# programmer_pcb2.net
KiCad netlist of a schematic drawn in EAGLE
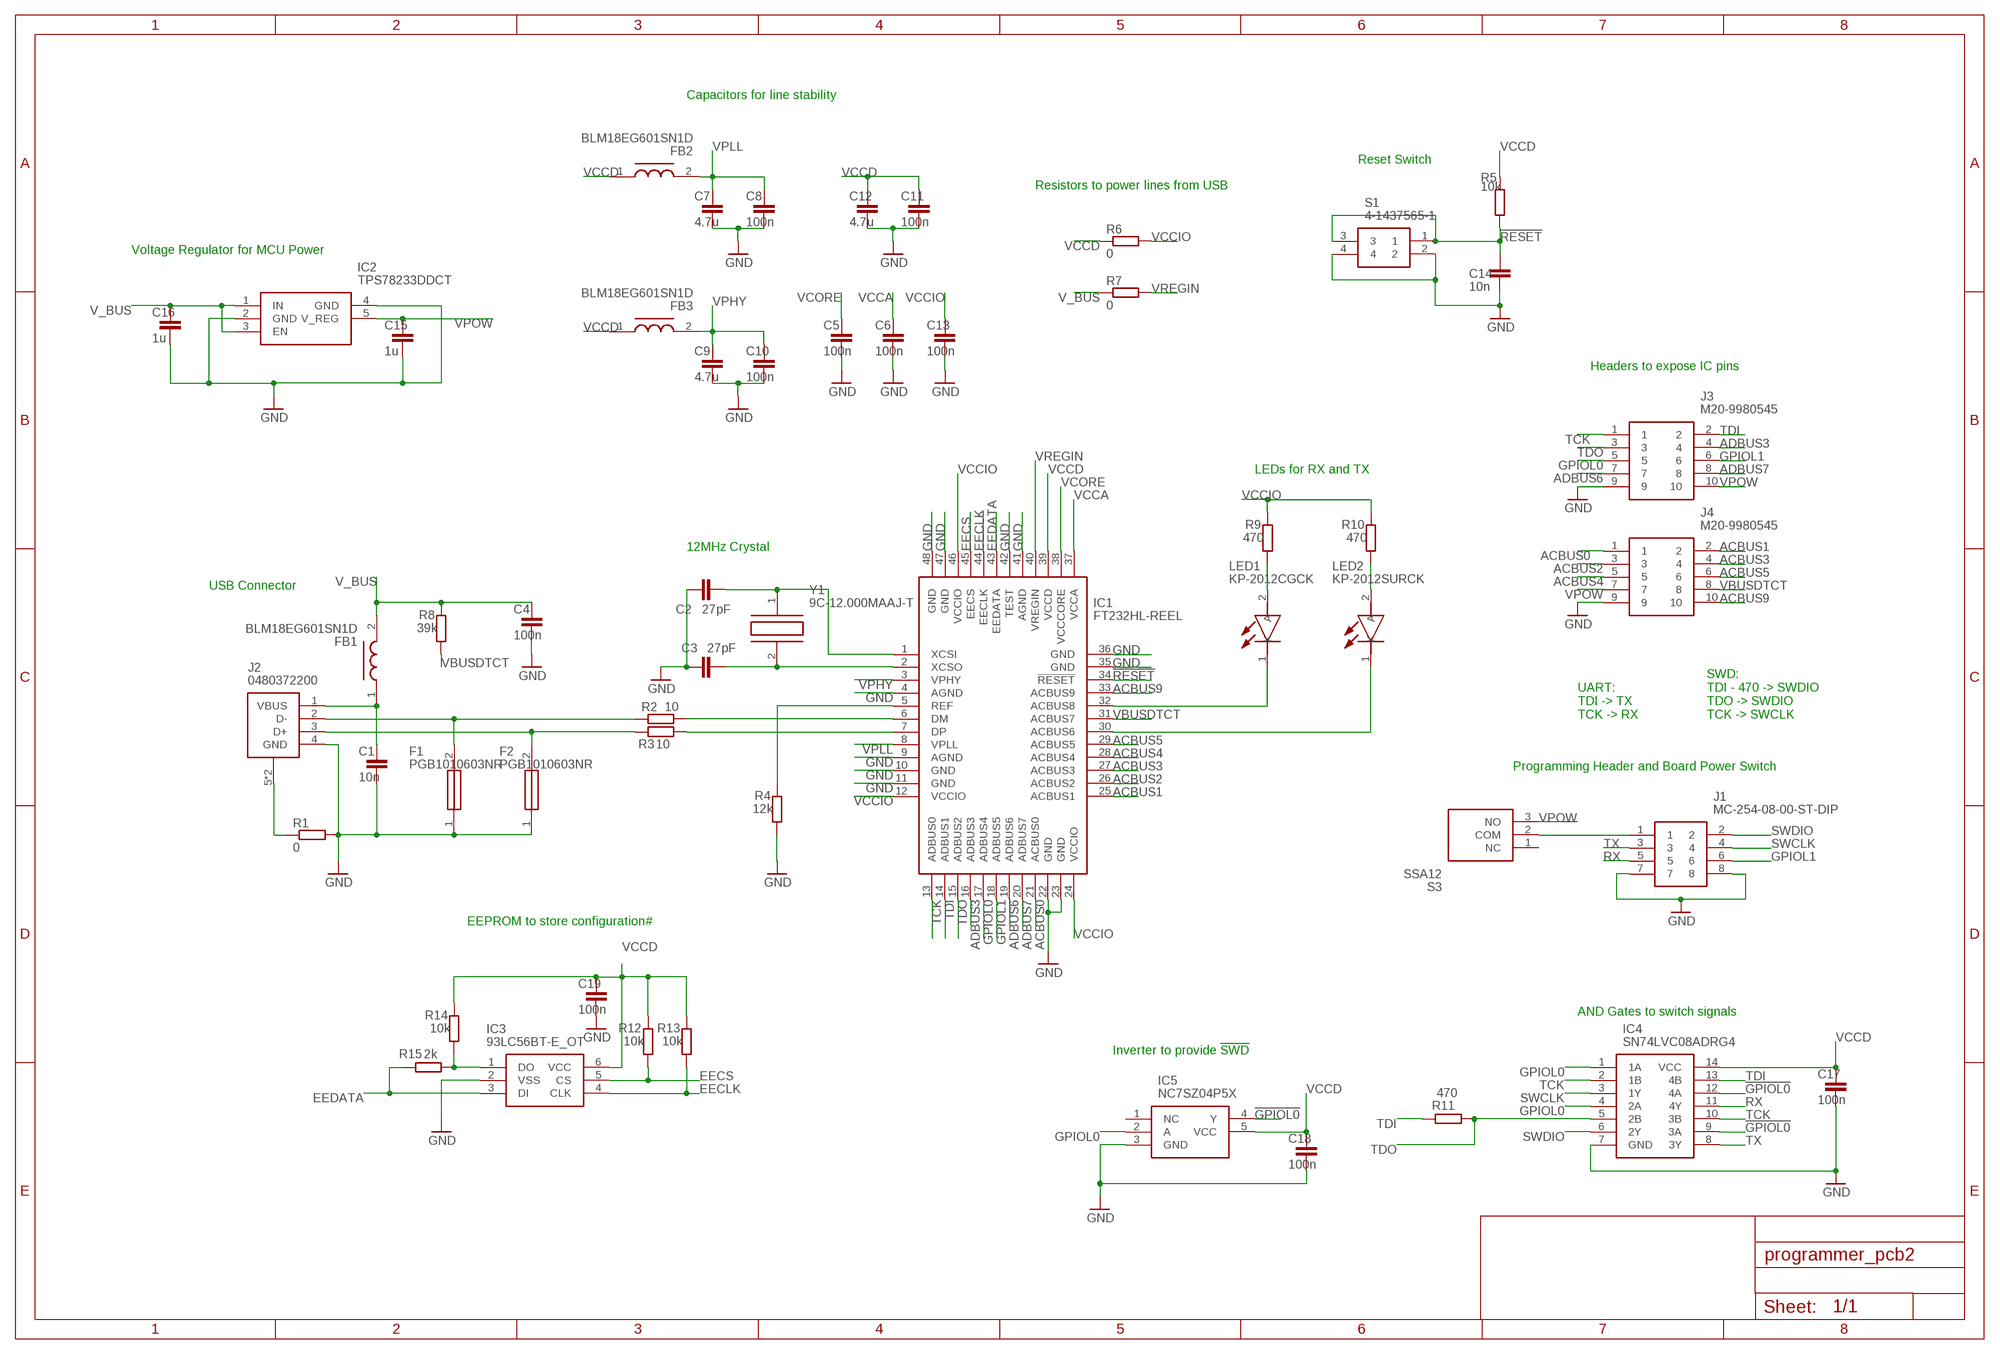
[diagram p0: schematic, sheet 1]

(export (version "E")
  (design (tool "Eeschema 10.0.6"))
  (components
    (comp (ref "C1")
      (value "10n")
      (footprint "eagle-import:C0805")
      (libsource (lib "eagle-import") (part "C-EUC0805"))
    )
    (comp (ref "C2")
      (value "27pF")
      (footprint "eagle-import:C0805")
      (libsource (lib "eagle-import") (part "C-EUC0805"))
    )
    (comp (ref "C3")
      (value "27pF")
      (footprint "eagle-import:C0805")
      (libsource (lib "eagle-import") (part "C-EUC0805"))
    )
    (comp (ref "C4")
      (value "100n")
      (footprint "eagle-import:C0805")
      (libsource (lib "eagle-import") (part "C-EUC0805"))
    )
    (comp (ref "C5")
      (value "100n")
      (footprint "eagle-import:C0805")
      (libsource (lib "eagle-import") (part "C-EUC0805"))
    )
    (comp (ref "C6")
      (value "100n")
      (footprint "eagle-import:C0805")
      (libsource (lib "eagle-import") (part "C-EUC0805"))
    )
    (comp (ref "C7")
      (value "4.7u")
      (footprint "eagle-import:C0805")
      (libsource (lib "eagle-import") (part "C-EUC0805"))
    )
    (comp (ref "C8")
      (value "100n")
      (footprint "eagle-import:C0805")
      (libsource (lib "eagle-import") (part "C-EUC0805"))
    )
    (comp (ref "C9")
      (value "4.7u")
      (footprint "eagle-import:C0805")
      (libsource (lib "eagle-import") (part "C-EUC0805"))
    )
    (comp (ref "C10")
      (value "100n")
      (footprint "eagle-import:C0805")
      (libsource (lib "eagle-import") (part "C-EUC0805"))
    )
    (comp (ref "C11")
      (value "100n")
      (footprint "eagle-import:C0805")
      (libsource (lib "eagle-import") (part "C-EUC0805"))
    )
    (comp (ref "C12")
      (value "4.7u")
      (footprint "eagle-import:C0805")
      (libsource (lib "eagle-import") (part "C-EUC0805"))
    )
    (comp (ref "C13")
      (value "100n")
      (footprint "eagle-import:C0805")
      (libsource (lib "eagle-import") (part "C-EUC0805"))
    )
    (comp (ref "C14")
      (value "10n")
      (footprint "eagle-import:C0805")
      (libsource (lib "eagle-import") (part "C-EUC0805"))
    )
    (comp (ref "C15")
      (value "1u")
      (footprint "eagle-import:C0805")
      (libsource (lib "eagle-import") (part "C-EUC0805"))
    )
    (comp (ref "C16")
      (value "1u")
      (footprint "eagle-import:C0805")
      (libsource (lib "eagle-import") (part "C-EUC0805"))
    )
    (comp (ref "C17")
      (value "100n")
      (footprint "eagle-import:C0805")
      (libsource (lib "eagle-import") (part "C-EUC0805"))
    )
    (comp (ref "C18")
      (value "100n")
      (footprint "eagle-import:C0805")
      (libsource (lib "eagle-import") (part "C-EUC0805"))
    )
    (comp (ref "C19")
      (value "100n")
      (footprint "eagle-import:C0805")
      (libsource (lib "eagle-import") (part "C-EUC0805"))
    )
    (comp (ref "F1")
      (value "PGB1010603NR")
      (footprint "eagle-import:FUSC1708X36N")
      (fields (field (name "MOUSER_PART_NUMBER") "576-PGB1010603NR"))
      (libsource (lib "eagle-import") (part "PGB1010603NR"))
    )
    (comp (ref "F2")
      (value "PGB1010603NR")
      (footprint "eagle-import:FUSC1708X36N")
      (fields (field (name "MOUSER_PART_NUMBER") "576-PGB1010603NR"))
      (libsource (lib "eagle-import") (part "PGB1010603NR"))
    )
    (comp (ref "FB1")
      (value "BLM18EG601SN1D")
      (footprint "eagle-import:BLM18EG121SH1D")
      (fields (field (name "MOUSER_PART_NUMBER") "81-BLM18EG601SN1D"))
      (libsource (lib "eagle-import") (part "BLM18EG601SN1D"))
    )
    (comp (ref "FB2")
      (value "BLM18EG601SN1D")
      (footprint "eagle-import:BLM18EG121SH1D")
      (fields (field (name "MOUSER_PART_NUMBER") "81-BLM18EG601SN1D"))
      (libsource (lib "eagle-import") (part "BLM18EG601SN1D"))
    )
    (comp (ref "FB3")
      (value "BLM18EG601SN1D")
      (footprint "eagle-import:BLM18EG121SH1D")
      (fields (field (name "MOUSER_PART_NUMBER") "81-BLM18EG601SN1D"))
      (libsource (lib "eagle-import") (part "BLM18EG601SN1D"))
    )
    (comp (ref "IC1")
      (value "FT232HL-REEL")
      (footprint "eagle-import:QFP50P900X900X160-48N")
      (fields (field (name "MOUSER_PART_NUMBER") "895-FT232HL-REEL"))
      (libsource (lib "eagle-import") (part "FT232HL-REEL"))
    )
    (comp (ref "IC2")
      (value "TPS78233DDCT")
      (footprint "eagle-import:SOT95P280X110-5N")
      (fields (field (name "MOUSER_PART_NUMBER") "595-TPS78233DDCT"))
      (libsource (lib "eagle-import") (part "TPS78233DDCT"))
    )
    (comp (ref "IC3")
      (value "93LC56BT-E_OT")
      (footprint "eagle-import:SOT95P270X145-6N")
      (fields
        (field (name "ARROW_PART_NUMBER") "93LC56BT-E/OT")
        (field (name "MOUSER_PART_NUMBER") "579-93LC56BT-E/OT")
      )
      (libsource (lib "eagle-import") (part "93LC56BT-E_OT"))
    )
    (comp (ref "IC4")
      (value "SN74LVC08ADRG4")
      (footprint "eagle-import:SOIC127P600X175-14N")
      (fields (field (name "MOUSER_PART_NUMBER") "595-SN74LVC08ADRG4"))
      (libsource (lib "eagle-import") (part "SN74LVC08ADRG4"))
    )
    (comp (ref "IC5")
      (value "NC7SZ04P5X")
      (footprint "eagle-import:SOT65P210X110-5N")
      (fields (field (name "MOUSER_PART_NUMBER") "512-NC7SZ04P5X"))
      (libsource (lib "eagle-import") (part "NC7SZ04P5X"))
    )
    (comp (ref "J1")
      (value "MC-254-08-00-ST-DIP")
      (footprint "eagle-import:MC2540800STDIP")
      (libsource (lib "eagle-import") (part "MC-254-08-00-ST-DIP"))
    )
    (comp (ref "J2")
      (value "0480372200")
      (footprint "eagle-import:0480372200")
      (libsource (lib "eagle-import") (part "0480372200"))
    )
    (comp (ref "J3")
      (value "M20-9980545")
      (footprint "eagle-import:HDRV10W80P254_2X5_1270X508X864")
      (fields (field (name "MOUSER_PART_NUMBER") "855-M20-9980545"))
      (libsource (lib "eagle-import") (part "M20-9980545"))
    )
    (comp (ref "J4")
      (value "M20-9980545")
      (footprint "eagle-import:HDRV10W80P254_2X5_1270X508X864")
      (fields (field (name "MOUSER_PART_NUMBER") "855-M20-9980545"))
      (libsource (lib "eagle-import") (part "M20-9980545"))
    )
    (comp (ref "LED1")
      (value "KP-2012CGCK")
      (footprint "eagle-import:LEDC2012X110N")
      (fields (field (name "RS_PART_NUMBER") "8610037P"))
      (libsource (lib "eagle-import") (part "KP-2012CGCK"))
    )
    (comp (ref "LED2")
      (value "KP-2012SURCK")
      (footprint "eagle-import:LEDC2012X110N")
      (fields
        (field (name "MANUFACTURER_PART_NUMBER") "KP-2012CGCK")
        (field (name "RS_PART_NUMBER") "8610037P")
      )
      (libsource (lib "eagle-import") (part "KP-2012SURCK"))
    )
    (comp (ref "R1")
      (value "0")
      (footprint "eagle-import:R0603")
      (libsource (lib "eagle-import") (part "R-EU_R0603"))
    )
    (comp (ref "R2")
      (value "10")
      (footprint "eagle-import:R0603")
      (libsource (lib "eagle-import") (part "R-EU_R0603"))
    )
    (comp (ref "R3")
      (value "10")
      (footprint "eagle-import:R0603")
      (libsource (lib "eagle-import") (part "R-EU_R0603"))
    )
    (comp (ref "R4")
      (value "12k")
      (footprint "eagle-import:R0603")
      (libsource (lib "eagle-import") (part "R-EU_R0603"))
    )
    (comp (ref "R5")
      (value "10k")
      (footprint "eagle-import:R0603")
      (libsource (lib "eagle-import") (part "R-EU_R0603"))
    )
    (comp (ref "R6")
      (value "0")
      (footprint "eagle-import:R0603")
      (libsource (lib "eagle-import") (part "R-EU_R0603"))
    )
    (comp (ref "R7")
      (value "0")
      (footprint "eagle-import:R0603")
      (libsource (lib "eagle-import") (part "R-EU_R0603"))
    )
    (comp (ref "R8")
      (value "39k")
      (footprint "eagle-import:R0603")
      (libsource (lib "eagle-import") (part "R-EU_R0603"))
    )
    (comp (ref "R9")
      (value "470")
      (footprint "eagle-import:R0603")
      (libsource (lib "eagle-import") (part "R-EU_R0603"))
    )
    (comp (ref "R10")
      (value "470")
      (footprint "eagle-import:R0603")
      (libsource (lib "eagle-import") (part "R-EU_R0603"))
    )
    (comp (ref "R11")
      (value "470")
      (footprint "eagle-import:R0603")
      (libsource (lib "eagle-import") (part "R-EU_R0603"))
    )
    (comp (ref "R12")
      (value "10k")
      (footprint "eagle-import:R0603")
      (libsource (lib "eagle-import") (part "R-EU_R0603"))
    )
    (comp (ref "R13")
      (value "10k")
      (footprint "eagle-import:R0603")
      (libsource (lib "eagle-import") (part "R-EU_R0603"))
    )
    (comp (ref "R14")
      (value "10k")
      (footprint "eagle-import:R0603")
      (libsource (lib "eagle-import") (part "R-EU_R0603"))
    )
    (comp (ref "R15")
      (value "2k")
      (footprint "eagle-import:R0603")
      (libsource (lib "eagle-import") (part "R-EU_R0603"))
    )
    (comp (ref "S1")
      (value "4-1437565-1")
      (footprint "eagle-import:FSM-SWITCH")
      (fields (field (name "RS_PART_NUMBER") "4791508P"))
      (libsource (lib "eagle-import") (part "4-1437565-1"))
    )
    (comp (ref "S3")
      (value "SSA12")
      (footprint "eagle-import:SSA12")
      (fields (field (name "RS_PART_NUMBER") "7182326P"))
      (libsource (lib "eagle-import") (part "SSA12"))
    )
    (comp (ref "Y1")
      (value "9C-12.000MAAJ-T")
      (footprint "eagle-import:SMD-HC-49-S")
      (fields
        (field (name "ARROW_PART_NUMBER") "9C-8.000MAAJ-T")
        (field (name "MOUSER_PART_NUMBER") "717-9C-8.000MAAJ-T")
      )
      (libsource (lib "eagle-import") (part "9C-12.000MAAJ-T"))
    )
  )
  (nets
    (net (code "1") (name "/ACBUS0") (class "Default")
      (node (ref "IC1") (pin "21") (pinfunction "ACBUS0_21") (pintype "bidirectional"))
      (node (ref "J4") (pin "1") (pinfunction "1_1") (pintype "bidirectional"))
    )
    (net (code "2") (name "/ACBUS1") (class "Default")
      (node (ref "IC1") (pin "25") (pinfunction "ACBUS1_25") (pintype "bidirectional"))
      (node (ref "J4") (pin "2") (pinfunction "2_2") (pintype "bidirectional"))
    )
    (net (code "3") (name "/ACBUS2") (class "Default")
      (node (ref "IC1") (pin "26") (pinfunction "ACBUS2_26") (pintype "bidirectional"))
      (node (ref "J4") (pin "3") (pinfunction "3_3") (pintype "bidirectional"))
    )
    (net (code "4") (name "/ACBUS3") (class "Default")
      (node (ref "IC1") (pin "27") (pinfunction "ACBUS3_27") (pintype "bidirectional"))
      (node (ref "J4") (pin "4") (pinfunction "4_4") (pintype "bidirectional"))
    )
    (net (code "5") (name "/ACBUS4") (class "Default")
      (node (ref "IC1") (pin "28") (pinfunction "ACBUS4_28") (pintype "bidirectional"))
      (node (ref "J4") (pin "5") (pinfunction "5_5") (pintype "bidirectional"))
    )
    (net (code "6") (name "/ACBUS5") (class "Default")
      (node (ref "IC1") (pin "29") (pinfunction "ACBUS5_29") (pintype "bidirectional"))
      (node (ref "J4") (pin "6") (pinfunction "6_6") (pintype "bidirectional"))
    )
    (net (code "7") (name "/ACBUS9") (class "Default")
      (node (ref "IC1") (pin "33") (pinfunction "ACBUS9_33") (pintype "bidirectional"))
      (node (ref "J4") (pin "10") (pinfunction "10_10") (pintype "bidirectional"))
    )
    (net (code "8") (name "/ADBUS3") (class "Default")
      (node (ref "IC1") (pin "16") (pinfunction "ADBUS3_16") (pintype "bidirectional"))
      (node (ref "J3") (pin "4") (pinfunction "4_4") (pintype "bidirectional"))
    )
    (net (code "9") (name "/ADBUS6") (class "Default")
      (node (ref "IC1") (pin "19") (pinfunction "ADBUS6_19") (pintype "bidirectional"))
      (node (ref "J3") (pin "7") (pinfunction "7_7") (pintype "bidirectional"))
    )
    (net (code "10") (name "/ADBUS7") (class "Default")
      (node (ref "IC1") (pin "20") (pinfunction "ADBUS7_20") (pintype "bidirectional"))
      (node (ref "J3") (pin "8") (pinfunction "8_8") (pintype "bidirectional"))
    )
    (net (code "11") (name "/EECLK") (class "Default")
      (node (ref "IC1") (pin "44") (pinfunction "EECLK_44") (pintype "input"))
      (node (ref "IC3") (pin "4") (pinfunction "CLK_4") (pintype "bidirectional"))
      (node (ref "R13") (pin "1") (pinfunction "1_1") (pintype "passive"))
    )
    (net (code "12") (name "/EECS") (class "Default")
      (node (ref "IC1") (pin "45") (pinfunction "EECS_45") (pintype "input"))
      (node (ref "IC3") (pin "5") (pinfunction "CS_5") (pintype "bidirectional"))
      (node (ref "R12") (pin "1") (pinfunction "1_1") (pintype "passive"))
    )
    (net (code "13") (name "/EEDATA") (class "Default")
      (node (ref "IC1") (pin "43") (pinfunction "EEDATA_43") (pintype "bidirectional"))
      (node (ref "IC3") (pin "3") (pinfunction "DI_3") (pintype "bidirectional"))
      (node (ref "R15") (pin "1") (pinfunction "1_1") (pintype "passive"))
    )
    (net (code "14") (name "/GPIOL0") (class "Default")
      (node (ref "IC1") (pin "17") (pinfunction "ADBUS4_17") (pintype "bidirectional"))
      (node (ref "IC4") (pin "1") (pinfunction "1A_1") (pintype "bidirectional"))
      (node (ref "IC4") (pin "4") (pinfunction "2A_4") (pintype "bidirectional"))
      (node (ref "IC5") (pin "2") (pinfunction "A_2") (pintype "bidirectional"))
      (node (ref "J3") (pin "5") (pinfunction "5_5") (pintype "bidirectional"))
    )
    (net (code "15") (name "/GPIOL1") (class "Default")
      (node (ref "IC1") (pin "18") (pinfunction "ADBUS5_18") (pintype "bidirectional"))
      (node (ref "J1") (pin "6") (pinfunction "6_6") (pintype "bidirectional"))
      (node (ref "J3") (pin "6") (pinfunction "6_6") (pintype "bidirectional"))
    )
    (net (code "16") (name "/RX") (class "Default")
      (node (ref "IC4") (pin "11") (pinfunction "4Y_11") (pintype "bidirectional"))
      (node (ref "J1") (pin "5") (pinfunction "5_5") (pintype "bidirectional"))
    )
    (net (code "17") (name "/SWCLK") (class "Default")
      (node (ref "IC4") (pin "3") (pinfunction "1Y_3") (pintype "bidirectional"))
      (node (ref "J1") (pin "4") (pinfunction "4_4") (pintype "bidirectional"))
    )
    (net (code "18") (name "/SWDIO") (class "Default")
      (node (ref "IC4") (pin "6") (pinfunction "2Y_6") (pintype "bidirectional"))
      (node (ref "J1") (pin "2") (pinfunction "2_2") (pintype "bidirectional"))
    )
    (net (code "19") (name "/TCK") (class "Default")
      (node (ref "IC1") (pin "13") (pinfunction "ADBUS0_13") (pintype "bidirectional"))
      (node (ref "IC4") (pin "10") (pinfunction "3B_10") (pintype "bidirectional"))
      (node (ref "IC4") (pin "2") (pinfunction "1B_2") (pintype "bidirectional"))
      (node (ref "J3") (pin "1") (pinfunction "1_1") (pintype "bidirectional"))
    )
    (net (code "20") (name "/TDI") (class "Default")
      (node (ref "IC1") (pin "14") (pinfunction "ADBUS1_14") (pintype "bidirectional"))
      (node (ref "IC4") (pin "13") (pinfunction "4B_13") (pintype "bidirectional"))
      (node (ref "J3") (pin "2") (pinfunction "2_2") (pintype "bidirectional"))
      (node (ref "R11") (pin "1") (pinfunction "1_1") (pintype "passive"))
    )
    (net (code "21") (name "/TDO") (class "Default")
      (node (ref "IC1") (pin "15") (pinfunction "ADBUS2_15") (pintype "bidirectional"))
      (node (ref "IC4") (pin "5") (pinfunction "2B_5") (pintype "bidirectional"))
      (node (ref "J3") (pin "3") (pinfunction "3_3") (pintype "bidirectional"))
      (node (ref "R11") (pin "2") (pinfunction "2_2") (pintype "passive"))
    )
    (net (code "22") (name "/TX") (class "Default")
      (node (ref "IC4") (pin "8") (pinfunction "3Y_8") (pintype "bidirectional"))
      (node (ref "J1") (pin "3") (pinfunction "3_3") (pintype "bidirectional"))
    )
    (net (code "23") (name "/VBUSDTCT") (class "Default")
      (node (ref "IC1") (pin "31") (pinfunction "ACBUS7_31") (pintype "bidirectional"))
      (node (ref "J4") (pin "8") (pinfunction "8_8") (pintype "bidirectional"))
      (node (ref "R8") (pin "1") (pinfunction "1_1") (pintype "passive"))
    )
    (net (code "24") (name "/VCCA") (class "Default")
      (node (ref "C6") (pin "1") (pinfunction "1_1") (pintype "passive"))
      (node (ref "IC1") (pin "37") (pinfunction "VCCA_37") (pintype "power_in"))
    )
    (net (code "25") (name "/VCCD") (class "Default")
      (node (ref "C11") (pin "1") (pinfunction "1_1") (pintype "passive"))
      (node (ref "C12") (pin "1") (pinfunction "1_1") (pintype "passive"))
      (node (ref "C17") (pin "1") (pinfunction "1_1") (pintype "passive"))
      (node (ref "C18") (pin "1") (pinfunction "1_1") (pintype "passive"))
      (node (ref "C19") (pin "1") (pinfunction "1_1") (pintype "passive"))
      (node (ref "FB2") (pin "1") (pinfunction "1_1") (pintype "bidirectional"))
      (node (ref "FB3") (pin "1") (pinfunction "1_1") (pintype "bidirectional"))
      (node (ref "IC1") (pin "39") (pinfunction "VCCD_39") (pintype "power_in"))
      (node (ref "IC3") (pin "6") (pinfunction "VCC_6") (pintype "bidirectional"))
      (node (ref "IC4") (pin "14") (pinfunction "VCC_14") (pintype "bidirectional"))
      (node (ref "IC5") (pin "5") (pinfunction "VCC_5") (pintype "bidirectional"))
      (node (ref "R12") (pin "2") (pinfunction "2_2") (pintype "passive"))
      (node (ref "R13") (pin "2") (pinfunction "2_2") (pintype "passive"))
      (node (ref "R14") (pin "2") (pinfunction "2_2") (pintype "passive"))
      (node (ref "R5") (pin "2") (pinfunction "2_2") (pintype "passive"))
      (node (ref "R6") (pin "1") (pinfunction "1_1") (pintype "passive"))
    )
    (net (code "26") (name "/VCCIO") (class "Default")
      (node (ref "C13") (pin "1") (pinfunction "1_1") (pintype "passive"))
      (node (ref "IC1") (pin "12") (pinfunction "VCCIO_12") (pintype "power_in"))
      (node (ref "IC1") (pin "24") (pinfunction "VCCIO_24") (pintype "power_in"))
      (node (ref "IC1") (pin "46") (pinfunction "VCCIO_46") (pintype "power_in"))
      (node (ref "R10") (pin "2") (pinfunction "2_2") (pintype "passive"))
      (node (ref "R6") (pin "2") (pinfunction "2_2") (pintype "passive"))
      (node (ref "R9") (pin "2") (pinfunction "2_2") (pintype "passive"))
    )
    (net (code "27") (name "/VCORE") (class "Default")
      (node (ref "C5") (pin "1") (pinfunction "1_1") (pintype "passive"))
      (node (ref "IC1") (pin "38") (pinfunction "VCCCORE_38") (pintype "power_in"))
    )
    (net (code "28") (name "/VPHY") (class "Default")
      (node (ref "C10") (pin "1") (pinfunction "1_1") (pintype "passive"))
      (node (ref "C9") (pin "1") (pinfunction "1_1") (pintype "passive"))
      (node (ref "FB3") (pin "2") (pinfunction "2_2") (pintype "bidirectional"))
      (node (ref "IC1") (pin "3") (pinfunction "VPHY_3") (pintype "bidirectional"))
    )
    (net (code "29") (name "/VPLL") (class "Default")
      (node (ref "C7") (pin "1") (pinfunction "1_1") (pintype "passive"))
      (node (ref "C8") (pin "1") (pinfunction "1_1") (pintype "passive"))
      (node (ref "FB2") (pin "2") (pinfunction "2_2") (pintype "bidirectional"))
      (node (ref "IC1") (pin "8") (pinfunction "VPLL_8") (pintype "bidirectional"))
    )
    (net (code "30") (name "/VPOW") (class "Default")
      (node (ref "C15") (pin "1") (pinfunction "1_1") (pintype "passive"))
      (node (ref "IC2") (pin "5") (pinfunction "V_REG_5") (pintype "power_in"))
      (node (ref "J3") (pin "10") (pinfunction "10_10") (pintype "bidirectional"))
      (node (ref "J4") (pin "7") (pinfunction "7_7") (pintype "bidirectional"))
      (node (ref "S3") (pin "3") (pinfunction "NO_3") (pintype "bidirectional"))
    )
    (net (code "31") (name "/VREGIN") (class "Default")
      (node (ref "IC1") (pin "40") (pinfunction "VREGIN_40") (pintype "input"))
      (node (ref "R7") (pin "2") (pinfunction "2_2") (pintype "passive"))
    )
    (net (code "32") (name "/V_BUS") (class "Default")
      (node (ref "C16") (pin "1") (pinfunction "1_1") (pintype "passive"))
      (node (ref "C4") (pin "1") (pinfunction "1_1") (pintype "passive"))
      (node (ref "FB1") (pin "2") (pinfunction "2_2") (pintype "bidirectional"))
      (node (ref "IC2") (pin "1") (pinfunction "IN_1") (pintype "input"))
      (node (ref "IC2") (pin "3") (pinfunction "EN_3") (pintype "bidirectional"))
      (node (ref "R7") (pin "1") (pinfunction "1_1") (pintype "passive"))
      (node (ref "R8") (pin "2") (pinfunction "2_2") (pintype "passive"))
    )
    (net (code "33") (name "/~{GPIOL0}") (class "Default")
      (node (ref "IC4") (pin "12") (pinfunction "4A_12") (pintype "bidirectional"))
      (node (ref "IC4") (pin "9") (pinfunction "3A_9") (pintype "bidirectional"))
      (node (ref "IC5") (pin "4") (pinfunction "Y_4") (pintype "bidirectional"))
    )
    (net (code "34") (name "/~{RESET}") (class "Default")
      (node (ref "C14") (pin "1") (pinfunction "1_1") (pintype "passive"))
      (node (ref "IC1") (pin "34") (pinfunction "~{RESET}_34") (pintype "bidirectional"))
      (node (ref "R5") (pin "1") (pinfunction "1_1") (pintype "passive"))
      (node (ref "S1") (pin "1") (pinfunction "1_1") (pintype "bidirectional"))
      (node (ref "S1") (pin "3") (pinfunction "3_3") (pintype "bidirectional"))
    )
    (net (code "35") (name "GND") (class "Default")
      (node (ref "C1") (pin "2") (pinfunction "2_2") (pintype "passive"))
      (node (ref "C10") (pin "2") (pinfunction "2_2") (pintype "passive"))
      (node (ref "C11") (pin "2") (pinfunction "2_2") (pintype "passive"))
      (node (ref "C12") (pin "2") (pinfunction "2_2") (pintype "passive"))
      (node (ref "C13") (pin "2") (pinfunction "2_2") (pintype "passive"))
      (node (ref "C14") (pin "2") (pinfunction "2_2") (pintype "passive"))
      (node (ref "C15") (pin "2") (pinfunction "2_2") (pintype "passive"))
      (node (ref "C16") (pin "2") (pinfunction "2_2") (pintype "passive"))
      (node (ref "C17") (pin "2") (pinfunction "2_2") (pintype "passive"))
      (node (ref "C18") (pin "2") (pinfunction "2_2") (pintype "passive"))
      (node (ref "C19") (pin "2") (pinfunction "2_2") (pintype "passive"))
      (node (ref "C2") (pin "1") (pinfunction "1_1") (pintype "passive"))
      (node (ref "C3") (pin "1") (pinfunction "1_1") (pintype "passive"))
      (node (ref "C4") (pin "2") (pinfunction "2_2") (pintype "passive"))
      (node (ref "C5") (pin "2") (pinfunction "2_2") (pintype "passive"))
      (node (ref "C6") (pin "2") (pinfunction "2_2") (pintype "passive"))
      (node (ref "C7") (pin "2") (pinfunction "2_2") (pintype "passive"))
      (node (ref "C8") (pin "2") (pinfunction "2_2") (pintype "passive"))
      (node (ref "C9") (pin "2") (pinfunction "2_2") (pintype "passive"))
      (node (ref "F1") (pin "1") (pinfunction "1_1") (pintype "bidirectional"))
      (node (ref "F2") (pin "1") (pinfunction "1_1") (pintype "bidirectional"))
      (node (ref "IC1") (pin "10") (pinfunction "GND_10") (pintype "power_in"))
      (node (ref "IC1") (pin "11") (pinfunction "GND_11") (pintype "power_in"))
      (node (ref "IC1") (pin "22") (pinfunction "GND_22") (pintype "power_in"))
      (node (ref "IC1") (pin "23") (pinfunction "GND_23") (pintype "power_in"))
      (node (ref "IC1") (pin "35") (pinfunction "GND_35") (pintype "power_in"))
      (node (ref "IC1") (pin "36") (pinfunction "GND_36") (pintype "power_in"))
      (node (ref "IC1") (pin "4") (pinfunction "AGND_4") (pintype "power_in"))
      (node (ref "IC1") (pin "41") (pinfunction "AGND_41") (pintype "power_in"))
      (node (ref "IC1") (pin "42") (pinfunction "TEST_42") (pintype "bidirectional"))
      (node (ref "IC1") (pin "47") (pinfunction "GND_47") (pintype "power_in"))
      (node (ref "IC1") (pin "48") (pinfunction "GND_48") (pintype "power_in"))
      (node (ref "IC1") (pin "9") (pinfunction "AGND_9") (pintype "power_in"))
      (node (ref "IC2") (pin "2") (pinfunction "GND_2") (pintype "power_in"))
      (node (ref "IC2") (pin "4") (pinfunction "GND_4") (pintype "power_in"))
      (node (ref "IC3") (pin "2") (pinfunction "VSS_2") (pintype "bidirectional"))
      (node (ref "IC4") (pin "7") (pinfunction "GND_7") (pintype "bidirectional"))
      (node (ref "IC5") (pin "3") (pinfunction "GND_3") (pintype "bidirectional"))
      (node (ref "J1") (pin "7") (pinfunction "7_7") (pintype "bidirectional"))
      (node (ref "J1") (pin "8") (pinfunction "8_8") (pintype "bidirectional"))
      (node (ref "J2") (pin "4") (pinfunction "GND_4") (pintype "bidirectional"))
      (node (ref "J3") (pin "9") (pinfunction "9_9") (pintype "bidirectional"))
      (node (ref "J4") (pin "9") (pinfunction "9_9") (pintype "bidirectional"))
      (node (ref "R1") (pin "2") (pinfunction "2_2") (pintype "passive"))
      (node (ref "R4") (pin "1") (pinfunction "1_1") (pintype "passive"))
      (node (ref "S1") (pin "2") (pinfunction "2_2") (pintype "bidirectional"))
      (node (ref "S1") (pin "4") (pinfunction "4_4") (pintype "bidirectional"))
    )
    (net (code "36") (name "Net-(IC1-ACBUS6)") (class "Default")
      (node (ref "IC1") (pin "30") (pinfunction "ACBUS6_30") (pintype "bidirectional"))
      (node (ref "LED2") (pin "1") (pinfunction "K_1") (pintype "bidirectional"))
    )
    (net (code "37") (name "Net-(IC1-ACBUS8)") (class "Default")
      (node (ref "IC1") (pin "32") (pinfunction "ACBUS8_32") (pintype "bidirectional"))
      (node (ref "LED1") (pin "1") (pinfunction "K_1") (pintype "bidirectional"))
    )
    (net (code "38") (name "Net-(IC1-DM)") (class "Default")
      (node (ref "IC1") (pin "6") (pinfunction "DM_6") (pintype "bidirectional"))
      (node (ref "R2") (pin "2") (pinfunction "2_2") (pintype "passive"))
    )
    (net (code "39") (name "Net-(IC1-DP)") (class "Default")
      (node (ref "IC1") (pin "7") (pinfunction "DP_7") (pintype "bidirectional"))
      (node (ref "R3") (pin "2") (pinfunction "2_2") (pintype "passive"))
    )
    (net (code "40") (name "Net-(IC1-REF)") (class "Default")
      (node (ref "IC1") (pin "5") (pinfunction "REF_5") (pintype "input"))
      (node (ref "R4") (pin "2") (pinfunction "2_2") (pintype "passive"))
    )
    (net (code "41") (name "Net-(IC1-XCSI)") (class "Default")
      (node (ref "C2") (pin "2") (pinfunction "2_2") (pintype "passive"))
      (node (ref "IC1") (pin "1") (pinfunction "XCSI_1") (pintype "input"))
      (node (ref "Y1") (pin "1") (pinfunction "1_1") (pintype "bidirectional"))
    )
    (net (code "42") (name "Net-(IC1-XCSO)") (class "Default")
      (node (ref "C3") (pin "2") (pinfunction "2_2") (pintype "passive"))
      (node (ref "IC1") (pin "2") (pinfunction "XCSO_2") (pintype "input"))
      (node (ref "Y1") (pin "2") (pinfunction "2_2") (pintype "bidirectional"))
    )
    (net (code "43") (name "Net-(IC3-DO)") (class "Default")
      (node (ref "IC3") (pin "1") (pinfunction "DO_1") (pintype "bidirectional"))
      (node (ref "R14") (pin "1") (pinfunction "1_1") (pintype "passive"))
      (node (ref "R15") (pin "2") (pinfunction "2_2") (pintype "passive"))
    )
    (net (code "44") (name "Net-(J2-D+)") (class "Default")
      (node (ref "F2") (pin "2") (pinfunction "2_2") (pintype "bidirectional"))
      (node (ref "J2") (pin "3") (pinfunction "D+_3") (pintype "bidirectional"))
      (node (ref "R3") (pin "1") (pinfunction "1_1") (pintype "passive"))
    )
    (net (code "45") (name "Net-(J2-D-)") (class "Default")
      (node (ref "F1") (pin "2") (pinfunction "2_2") (pintype "bidirectional"))
      (node (ref "J2") (pin "2") (pinfunction "D-_2") (pintype "bidirectional"))
      (node (ref "R2") (pin "1") (pinfunction "1_1") (pintype "passive"))
    )
    (net (code "46") (name "Net-(J2-SLD-Pad5)") (class "Default")
      (node (ref "J2") (pin "5") (pinfunction "SLD_5") (pintype "bidirectional"))
      (node (ref "J2") (pin "6") (pinfunction "SLD_6") (pintype "bidirectional"))
      (node (ref "R1") (pin "1") (pinfunction "1_1") (pintype "passive"))
    )
    (net (code "47") (name "Net-(J2-VBUS)") (class "Default")
      (node (ref "C1") (pin "1") (pinfunction "1_1") (pintype "passive"))
      (node (ref "FB1") (pin "1") (pinfunction "1_1") (pintype "bidirectional"))
      (node (ref "J2") (pin "1") (pinfunction "VBUS_1") (pintype "bidirectional"))
    )
    (net (code "48") (name "Net-(LED1-A)") (class "Default")
      (node (ref "LED1") (pin "2") (pinfunction "A_2") (pintype "bidirectional"))
      (node (ref "R9") (pin "1") (pinfunction "1_1") (pintype "passive"))
    )
    (net (code "49") (name "Net-(LED2-A)") (class "Default")
      (node (ref "LED2") (pin "2") (pinfunction "A_2") (pintype "bidirectional"))
      (node (ref "R10") (pin "1") (pinfunction "1_1") (pintype "passive"))
    )
    (net (code "50") (name "Net-(S3-COM)") (class "Default")
      (node (ref "J1") (pin "1") (pinfunction "1_1") (pintype "bidirectional"))
      (node (ref "S3") (pin "2") (pinfunction "COM_2") (pintype "bidirectional"))
    )
    (net (code "51") (name "unconnected-(IC5-NC-Pad1)") (class "Default")
      (node (ref "IC5") (pin "1") (pinfunction "NC_1") (pintype "no_connect"))
    )
    (net (code "52") (name "unconnected-(S3-NC-Pad1)") (class "Default")
      (node (ref "S3") (pin "1") (pinfunction "NC_1") (pintype "no_connect"))
    )
  )
)
